# Main_Board_Smart_Door.net
KiCad netlist of a schematic drawn in EAGLE
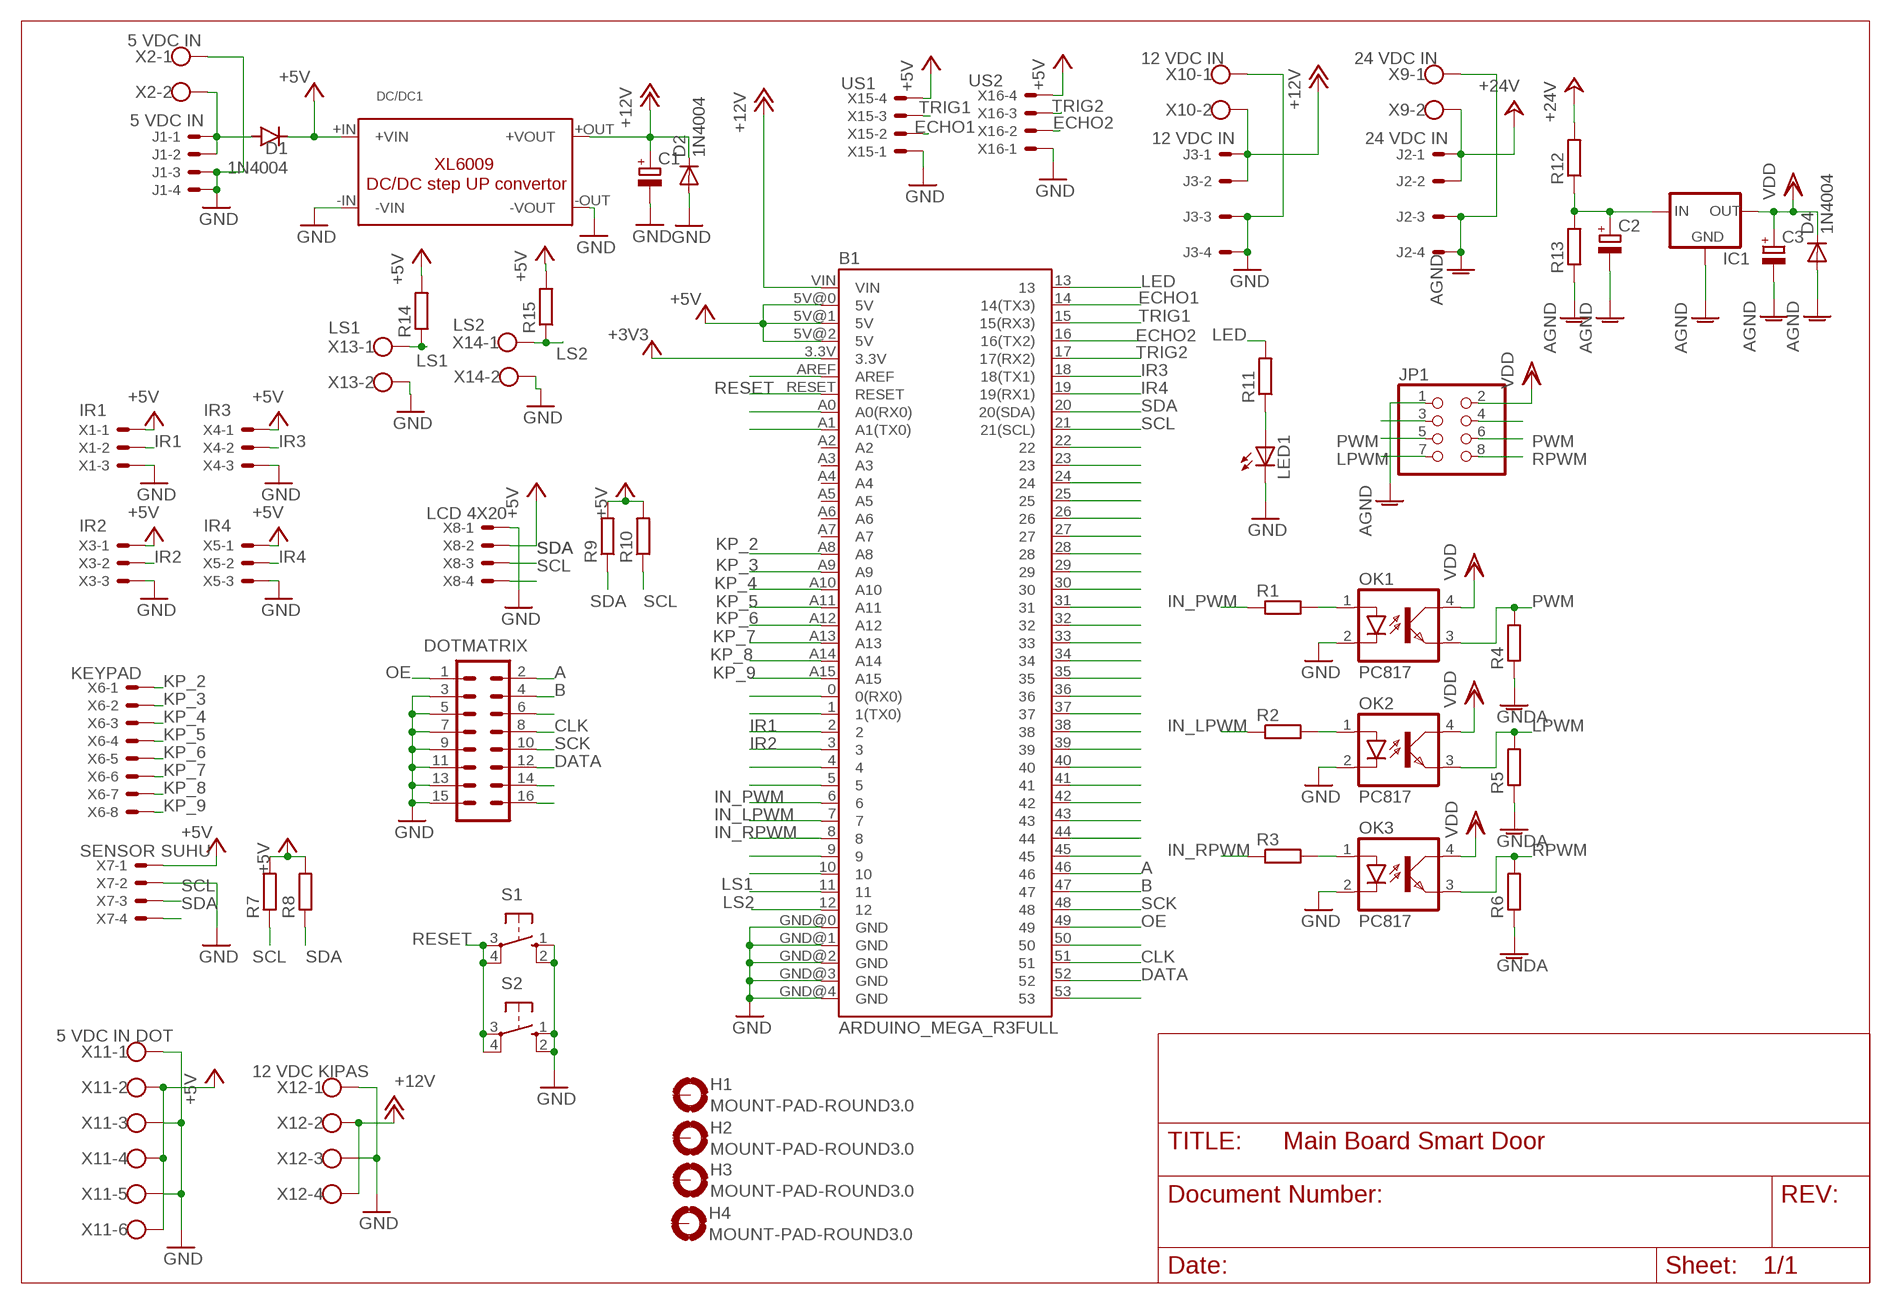
[diagram p0: schematic, sheet 1]

(export (version "E")
  (design (tool "Eeschema 10.0.6"))
  (components
    (comp (ref "B1")
      (value "ARDUINO_MEGA_R3FULL")
      (footprint "eagle-import:ARDUINO_MEGA")
      (libsource (lib "eagle-import") (part "ARDUINO_MEGA_R3FULL"))
    )
    (comp (ref "C1")
      (value "C-POL_RADIAL-25MM-DIA")
      (footprint "eagle-import:CAPPRD550W110D1250H2500B")
      (libsource (lib "eagle-import") (part "C-POLRADIAL-25MM-DIA_"))
    )
    (comp (ref "C2")
      (value "C-POL_RADIAL-25MM-DIA")
      (footprint "eagle-import:CAPPRD550W110D1250H2500B")
      (libsource (lib "eagle-import") (part "C-POLRADIAL-25MM-DIA_"))
    )
    (comp (ref "C3")
      (value "C-POL_RADIAL-25MM-DIA")
      (footprint "eagle-import:CAPPRD550W110D1250H2500B")
      (libsource (lib "eagle-import") (part "C-POLRADIAL-25MM-DIA_"))
    )
    (comp (ref "D1")
      (value "1N4004")
      (footprint "eagle-import:DO41-10")
      (libsource (lib "eagle-import") (part "diode_210_1N4004"))
    )
    (comp (ref "D2")
      (value "1N4004")
      (footprint "eagle-import:DO41-10")
      (libsource (lib "eagle-import") (part "1N4004"))
    )
    (comp (ref "D4")
      (value "1N4004")
      (footprint "eagle-import:DO41-10")
      (libsource (lib "eagle-import") (part "1N4004"))
    )
    (comp (ref "DC/DC1")
      (value "DC/DC-STEP-UP-XL6009")
      (footprint "eagle-import:DC_DC-STEP-UP-XL6009")
      (libsource (lib "eagle-import") (part "DC/DC-STEP-UP-XL6009"))
    )
    (comp (ref "DOTMATRIX")
      (value "ML16")
      (footprint "eagle-import:ML16")
      (libsource (lib "eagle-import") (part "ML16"))
    )
    (comp (ref "H1")
      (value "MOUNT-PAD-ROUND3.0")
      (footprint "eagle-import:3,0-PAD")
      (libsource (lib "eagle-import") (part "MOUNT-PAD-ROUND3.0"))
    )
    (comp (ref "H2")
      (value "MOUNT-PAD-ROUND3.0")
      (footprint "eagle-import:3,0-PAD")
      (libsource (lib "eagle-import") (part "MOUNT-PAD-ROUND3.0"))
    )
    (comp (ref "H3")
      (value "MOUNT-PAD-ROUND3.0")
      (footprint "eagle-import:3,0-PAD")
      (libsource (lib "eagle-import") (part "MOUNT-PAD-ROUND3.0"))
    )
    (comp (ref "H4")
      (value "MOUNT-PAD-ROUND3.0")
      (footprint "eagle-import:3,0-PAD")
      (libsource (lib "eagle-import") (part "MOUNT-PAD-ROUND3.0"))
    )
    (comp (ref "IC1")
      (value "78XXL")
      (footprint "eagle-import:78XXL")
      (libsource (lib "eagle-import") (part "78XXL"))
    )
    (comp (ref "J1")
      (value "5 VDC IN")
      (footprint "eagle-import:6410-04")
      (fields (field (name "MF") "MOLEX"))
      (libsource (lib "eagle-import") (part "22-?-0427-2041"))
    )
    (comp (ref "J2")
      (value "24 VDC IN")
      (footprint "eagle-import:6410-04")
      (fields (field (name "MF") "MOLEX"))
      (libsource (lib "eagle-import") (part "22-?-0427-2041"))
    )
    (comp (ref "J3")
      (value "12 VDC IN")
      (footprint "eagle-import:6410-04")
      (fields (field (name "MF") "MOLEX"))
      (libsource (lib "eagle-import") (part "22-?-0427-2041"))
    )
    (comp (ref "JP1")
      (value "PINHD-2X4")
      (footprint "eagle-import:2X04")
      (libsource (lib "eagle-import") (part "PINHD-2X4"))
    )
    (comp (ref "LED1")
      (value "LED5MM")
      (footprint "eagle-import:LED5MM")
      (libsource (lib "eagle-import") (part "LED5MM"))
    )
    (comp (ref "OK1")
      (value "PC817")
      (footprint "eagle-import:DIL04")
      (fields (field (name "MPN") "PC817X4J000F"))
      (libsource (lib "eagle-import") (part "PC817"))
    )
    (comp (ref "OK2")
      (value "PC817")
      (footprint "eagle-import:DIL04")
      (fields (field (name "MPN") "PC817X4J000F"))
      (libsource (lib "eagle-import") (part "PC817"))
    )
    (comp (ref "OK3")
      (value "PC817")
      (footprint "eagle-import:DIL04")
      (fields (field (name "MPN") "PC817X4J000F"))
      (libsource (lib "eagle-import") (part "PC817"))
    )
    (comp (ref "R1")
      (value "R-EU_0207/10")
      (footprint "eagle-import:0207_10")
      (libsource (lib "eagle-import") (part "R-EU_0207/10"))
    )
    (comp (ref "R2")
      (value "R-EU_0207/10")
      (footprint "eagle-import:0207_10")
      (libsource (lib "eagle-import") (part "R-EU_0207/10"))
    )
    (comp (ref "R3")
      (value "R-EU_0207/10")
      (footprint "eagle-import:0207_10")
      (libsource (lib "eagle-import") (part "R-EU_0207/10"))
    )
    (comp (ref "R4")
      (value "R-EU_0207/10")
      (footprint "eagle-import:0207_10")
      (libsource (lib "eagle-import") (part "R-EU_0207/10"))
    )
    (comp (ref "R5")
      (value "R-EU_0207/10")
      (footprint "eagle-import:0207_10")
      (libsource (lib "eagle-import") (part "R-EU_0207/10"))
    )
    (comp (ref "R6")
      (value "R-EU_0207/10")
      (footprint "eagle-import:0207_10")
      (libsource (lib "eagle-import") (part "R-EU_0207/10"))
    )
    (comp (ref "R7")
      (value "R-EU_0207/10")
      (footprint "eagle-import:0207_10")
      (libsource (lib "eagle-import") (part "R-EU_0207/10"))
    )
    (comp (ref "R8")
      (value "R-EU_0207/10")
      (footprint "eagle-import:0207_10")
      (libsource (lib "eagle-import") (part "R-EU_0207/10"))
    )
    (comp (ref "R9")
      (value "R-EU_0207/10")
      (footprint "eagle-import:0207_10")
      (libsource (lib "eagle-import") (part "R-EU_0207/10"))
    )
    (comp (ref "R10")
      (value "R-EU_0207/10")
      (footprint "eagle-import:0207_10")
      (libsource (lib "eagle-import") (part "R-EU_0207/10"))
    )
    (comp (ref "R11")
      (value "R-EU_0207/10")
      (footprint "eagle-import:0207_10")
      (libsource (lib "eagle-import") (part "R-EU_0207/10"))
    )
    (comp (ref "R12")
      (value "R-EU_0207/10")
      (footprint "eagle-import:0207_10")
      (libsource (lib "eagle-import") (part "R-EU_0207/10"))
    )
    (comp (ref "R13")
      (value "R-EU_0207/10")
      (footprint "eagle-import:0207_10")
      (libsource (lib "eagle-import") (part "R-EU_0207/10"))
    )
    (comp (ref "R14")
      (value "R-EU_0207/10")
      (footprint "eagle-import:0207_10")
      (libsource (lib "eagle-import") (part "R-EU_0207/10"))
    )
    (comp (ref "R15")
      (value "R-EU_0207/10")
      (footprint "eagle-import:0207_10")
      (libsource (lib "eagle-import") (part "R-EU_0207/10"))
    )
    (comp (ref "S1")
      (value "40-XX")
      (footprint "eagle-import:B3F-40XX")
      (fields (field (name "MF") "OMRON COMPONENTS USA") (field (name "MPN") "B3F-4000"))
      (libsource (lib "eagle-import") (part "40-XX"))
    )
    (comp (ref "S2")
      (value "10-XX")
      (footprint "eagle-import:B3F-10XX")
      (fields (field (name "MPN") "B3F-1000"))
      (libsource (lib "eagle-import") (part "10-XX"))
    )
    (comp (ref "X1")
      (value "IR1")
      (footprint "eagle-import:JST-XH-03-PACKAGE-LONG-PAD")
      (libsource (lib "eagle-import") (part "JST-XH-03-PIN-LONG-PAD"))
    )
    (comp (ref "X2")
      (value "5 VDC IN")
      (footprint "eagle-import:W237-102")
      (fields (field (name "MPN") "237-102"))
      (libsource (lib "eagle-import") (part "W237-102"))
    )
    (comp (ref "X3")
      (value "IR2")
      (footprint "eagle-import:JST-XH-03-PACKAGE-LONG-PAD")
      (libsource (lib "eagle-import") (part "JST-XH-03-PIN-LONG-PAD"))
    )
    (comp (ref "X4")
      (value "IR3")
      (footprint "eagle-import:JST-XH-03-PACKAGE-LONG-PAD")
      (libsource (lib "eagle-import") (part "JST-XH-03-PIN-LONG-PAD"))
    )
    (comp (ref "X5")
      (value "IR4")
      (footprint "eagle-import:JST-XH-03-PACKAGE-LONG-PAD")
      (libsource (lib "eagle-import") (part "JST-XH-03-PIN-LONG-PAD"))
    )
    (comp (ref "X6")
      (value "KEYPAD")
      (footprint "eagle-import:JST-XH-08-PACKAGE-LONG-PAD")
      (libsource (lib "eagle-import") (part "JST-XH-08-PIN-LONG-PAD"))
    )
    (comp (ref "X7")
      (value "SENSOR SUHU")
      (footprint "eagle-import:JST-XH-04-PACKAGE-LONG-PAD")
      (libsource (lib "eagle-import") (part "JST-XH-04-PIN-LONG-PAD"))
    )
    (comp (ref "X8")
      (value "LCD 4X20")
      (footprint "eagle-import:JST-XH-04-PACKAGE-LONG-PAD")
      (libsource (lib "eagle-import") (part "JST-XH-04-PIN-LONG-PAD"))
    )
    (comp (ref "X9")
      (value "24 VDC IN")
      (footprint "eagle-import:W237-102")
      (fields (field (name "MPN") "237-102"))
      (libsource (lib "eagle-import") (part "W237-102"))
    )
    (comp (ref "X10")
      (value "12 VDC IN")
      (footprint "eagle-import:W237-102")
      (fields (field (name "MPN") "237-102"))
      (libsource (lib "eagle-import") (part "W237-102"))
    )
    (comp (ref "X11")
      (value "5 VDC IN DOT")
      (footprint "eagle-import:W237-6")
      (libsource (lib "eagle-import") (part "W237-6"))
    )
    (comp (ref "X12")
      (value "12 VDC KIPAS")
      (footprint "eagle-import:W237-4")
      (libsource (lib "eagle-import") (part "W237-4"))
    )
    (comp (ref "X13")
      (value "LS1")
      (footprint "eagle-import:W237-102")
      (fields (field (name "MPN") "237-102"))
      (libsource (lib "eagle-import") (part "W237-102"))
    )
    (comp (ref "X14")
      (value "LS2")
      (footprint "eagle-import:W237-102")
      (fields (field (name "MPN") "237-102"))
      (libsource (lib "eagle-import") (part "W237-102"))
    )
    (comp (ref "X15")
      (value "US1")
      (footprint "eagle-import:JST-XH-04-PACKAGE-LONG-PAD")
      (libsource (lib "eagle-import") (part "JST-XH-04-PIN-LONG-PAD"))
    )
    (comp (ref "X16")
      (value "US2")
      (footprint "eagle-import:JST-XH-04-PACKAGE-LONG-PAD")
      (libsource (lib "eagle-import") (part "JST-XH-04-PIN-LONG-PAD"))
    )
  )
  (nets
    (net (code "1") (name "+3V3") (class "Default")
      (node (ref "B1") (pin "3.3V") (pinfunction "3.3V_3.3V") (pintype "bidirectional"))
    )
    (net (code "2") (name "+5V") (class "Default")
      (node (ref "B1") (pin "5V@0") (pinfunction "5V_5V@0") (pintype "bidirectional"))
      (node (ref "B1") (pin "5V@1") (pinfunction "5V_5V@1") (pintype "bidirectional"))
      (node (ref "B1") (pin "5V@2") (pinfunction "5V_5V@2") (pintype "bidirectional"))
      (node (ref "D1") (pin "C") (pinfunction "C_C") (pintype "passive"))
      (node (ref "DC/DC1") (pin "+IN") (pinfunction "+VIN_+IN") (pintype "bidirectional"))
      (node (ref "R10") (pin "2") (pinfunction "2_2") (pintype "passive"))
      (node (ref "R14") (pin "2") (pinfunction "2_2") (pintype "passive"))
      (node (ref "R15") (pin "2") (pinfunction "2_2") (pintype "passive"))
      (node (ref "R7") (pin "2") (pinfunction "2_2") (pintype "passive"))
      (node (ref "R8") (pin "2") (pinfunction "2_2") (pintype "passive"))
      (node (ref "R9") (pin "2") (pinfunction "2_2") (pintype "passive"))
      (node (ref "X1") (pin "1") (pinfunction "S_1") (pintype "passive"))
      (node (ref "X11") (pin "2") (pinfunction "KL_2") (pintype "passive"))
      (node (ref "X11") (pin "4") (pinfunction "KL_4") (pintype "passive"))
      (node (ref "X11") (pin "6") (pinfunction "KL_6") (pintype "passive"))
      (node (ref "X15") (pin "4") (pinfunction "S_4") (pintype "passive"))
      (node (ref "X16") (pin "4") (pinfunction "S_4") (pintype "passive"))
      (node (ref "X3") (pin "1") (pinfunction "S_1") (pintype "passive"))
      (node (ref "X4") (pin "1") (pinfunction "S_1") (pintype "passive"))
      (node (ref "X5") (pin "1") (pinfunction "S_1") (pintype "passive"))
      (node (ref "X7") (pin "1") (pinfunction "S_1") (pintype "passive"))
      (node (ref "X8") (pin "2") (pinfunction "S_2") (pintype "passive"))
    )
    (net (code "3") (name "+12V") (class "Default")
      (node (ref "B1") (pin "VIN") (pinfunction "VIN_VIN") (pintype "bidirectional"))
      (node (ref "C1") (pin "1") (pinfunction "+_1") (pintype "passive"))
      (node (ref "D2") (pin "C") (pinfunction "C_C") (pintype "passive"))
      (node (ref "DC/DC1") (pin "+OUT") (pinfunction "+VOUT_+OUT") (pintype "bidirectional"))
      (node (ref "J3") (pin "1") (pinfunction "S_1") (pintype "passive"))
      (node (ref "J3") (pin "2") (pinfunction "S_2") (pintype "passive"))
      (node (ref "X10") (pin "2") (pinfunction "KL_2") (pintype "passive"))
      (node (ref "X12") (pin "2") (pinfunction "KL_2") (pintype "passive"))
      (node (ref "X12") (pin "4") (pinfunction "KL_4") (pintype "passive"))
    )
    (net (code "4") (name "+24V") (class "Default")
      (node (ref "J2") (pin "1") (pinfunction "S_1") (pintype "passive"))
      (node (ref "J2") (pin "2") (pinfunction "S_2") (pintype "passive"))
      (node (ref "R12") (pin "2") (pinfunction "2_2") (pintype "passive"))
      (node (ref "X9") (pin "2") (pinfunction "KL_2") (pintype "passive"))
    )
    (net (code "5") (name "/A") (class "Default")
      (node (ref "B1") (pin "46") (pinfunction "46_46") (pintype "bidirectional"))
      (node (ref "DOTMATRIX") (pin "2") (pinfunction "2_2") (pintype "passive"))
    )
    (net (code "6") (name "/B") (class "Default")
      (node (ref "B1") (pin "47") (pinfunction "47_47") (pintype "bidirectional"))
      (node (ref "DOTMATRIX") (pin "4") (pinfunction "4_4") (pintype "passive"))
    )
    (net (code "7") (name "/CLK") (class "Default")
      (node (ref "B1") (pin "51") (pinfunction "51_51") (pintype "bidirectional"))
      (node (ref "DOTMATRIX") (pin "8") (pinfunction "8_8") (pintype "passive"))
    )
    (net (code "8") (name "/DATA") (class "Default")
      (node (ref "B1") (pin "52") (pinfunction "52_52") (pintype "bidirectional"))
      (node (ref "DOTMATRIX") (pin "12") (pinfunction "12_12") (pintype "passive"))
    )
    (net (code "9") (name "/ECHO1") (class "Default")
      (node (ref "B1") (pin "14") (pinfunction "14(TX3)_14") (pintype "bidirectional"))
      (node (ref "X15") (pin "2") (pinfunction "S_2") (pintype "passive"))
    )
    (net (code "10") (name "/ECHO2") (class "Default")
      (node (ref "B1") (pin "16") (pinfunction "16(TX2)_16") (pintype "bidirectional"))
      (node (ref "X16") (pin "2") (pinfunction "S_2") (pintype "passive"))
    )
    (net (code "11") (name "/IN_LPWM") (class "Default")
      (node (ref "B1") (pin "7") (pinfunction "7_7") (pintype "bidirectional"))
      (node (ref "R2") (pin "1") (pinfunction "1_1") (pintype "passive"))
    )
    (net (code "12") (name "/IN_PWM") (class "Default")
      (node (ref "B1") (pin "6") (pinfunction "6_6") (pintype "bidirectional"))
      (node (ref "R1") (pin "1") (pinfunction "1_1") (pintype "passive"))
    )
    (net (code "13") (name "/IN_RPWM") (class "Default")
      (node (ref "B1") (pin "8") (pinfunction "8_8") (pintype "bidirectional"))
      (node (ref "R3") (pin "1") (pinfunction "1_1") (pintype "passive"))
    )
    (net (code "14") (name "/IR1") (class "Default")
      (node (ref "B1") (pin "2") (pinfunction "2_2") (pintype "bidirectional"))
      (node (ref "X1") (pin "2") (pinfunction "S_2") (pintype "passive"))
    )
    (net (code "15") (name "/IR2") (class "Default")
      (node (ref "B1") (pin "3") (pinfunction "3_3") (pintype "bidirectional"))
      (node (ref "X3") (pin "2") (pinfunction "S_2") (pintype "passive"))
    )
    (net (code "16") (name "/IR3") (class "Default")
      (node (ref "B1") (pin "18") (pinfunction "18(TX1)_18") (pintype "bidirectional"))
      (node (ref "X4") (pin "2") (pinfunction "S_2") (pintype "passive"))
    )
    (net (code "17") (name "/IR4") (class "Default")
      (node (ref "B1") (pin "19") (pinfunction "19(RX1)_19") (pintype "bidirectional"))
      (node (ref "X5") (pin "2") (pinfunction "S_2") (pintype "passive"))
    )
    (net (code "18") (name "/KP_2") (class "Default")
      (node (ref "B1") (pin "A8") (pinfunction "A8_A8") (pintype "bidirectional"))
      (node (ref "X6") (pin "1") (pinfunction "S_1") (pintype "passive"))
    )
    (net (code "19") (name "/KP_3") (class "Default")
      (node (ref "B1") (pin "A9") (pinfunction "A9_A9") (pintype "bidirectional"))
      (node (ref "X6") (pin "2") (pinfunction "S_2") (pintype "passive"))
    )
    (net (code "20") (name "/KP_4") (class "Default")
      (node (ref "B1") (pin "A10") (pinfunction "A10_A10") (pintype "bidirectional"))
      (node (ref "X6") (pin "3") (pinfunction "S_3") (pintype "passive"))
    )
    (net (code "21") (name "/KP_5") (class "Default")
      (node (ref "B1") (pin "A11") (pinfunction "A11_A11") (pintype "bidirectional"))
      (node (ref "X6") (pin "4") (pinfunction "S_4") (pintype "passive"))
    )
    (net (code "22") (name "/KP_6") (class "Default")
      (node (ref "B1") (pin "A12") (pinfunction "A12_A12") (pintype "bidirectional"))
      (node (ref "X6") (pin "5") (pinfunction "S_5") (pintype "passive"))
    )
    (net (code "23") (name "/KP_7") (class "Default")
      (node (ref "B1") (pin "A13") (pinfunction "A13_A13") (pintype "bidirectional"))
      (node (ref "X6") (pin "6") (pinfunction "S_6") (pintype "passive"))
    )
    (net (code "24") (name "/KP_8") (class "Default")
      (node (ref "B1") (pin "A14") (pinfunction "A14_A14") (pintype "bidirectional"))
      (node (ref "X6") (pin "7") (pinfunction "S_7") (pintype "passive"))
    )
    (net (code "25") (name "/KP_9") (class "Default")
      (node (ref "B1") (pin "A15") (pinfunction "A15_A15") (pintype "bidirectional"))
      (node (ref "X6") (pin "8") (pinfunction "S_8") (pintype "passive"))
    )
    (net (code "26") (name "/LED") (class "Default")
      (node (ref "B1") (pin "13") (pinfunction "13_13") (pintype "bidirectional"))
      (node (ref "R11") (pin "2") (pinfunction "2_2") (pintype "passive"))
    )
    (net (code "27") (name "/LPWM") (class "Default")
      (node (ref "JP1") (pin "7") (pinfunction "7_7") (pintype "passive"))
      (node (ref "OK2") (pin "3") (pinfunction "EMIT_3") (pintype "passive"))
      (node (ref "R5") (pin "2") (pinfunction "2_2") (pintype "passive"))
    )
    (net (code "28") (name "/LS1") (class "Default")
      (node (ref "B1") (pin "11") (pinfunction "11_11") (pintype "bidirectional"))
      (node (ref "R14") (pin "1") (pinfunction "1_1") (pintype "passive"))
      (node (ref "X13") (pin "1") (pinfunction "KL_1") (pintype "passive"))
    )
    (net (code "29") (name "/LS2") (class "Default")
      (node (ref "B1") (pin "12") (pinfunction "12_12") (pintype "bidirectional"))
      (node (ref "R15") (pin "1") (pinfunction "1_1") (pintype "passive"))
      (node (ref "X14") (pin "1") (pinfunction "KL_1") (pintype "passive"))
    )
    (net (code "30") (name "/OE") (class "Default")
      (node (ref "B1") (pin "49") (pinfunction "49_49") (pintype "bidirectional"))
      (node (ref "DOTMATRIX") (pin "1") (pinfunction "1_1") (pintype "passive"))
    )
    (net (code "31") (name "/PWM") (class "Default")
      (node (ref "JP1") (pin "5") (pinfunction "5_5") (pintype "passive"))
      (node (ref "JP1") (pin "6") (pinfunction "6_6") (pintype "passive"))
      (node (ref "OK1") (pin "3") (pinfunction "EMIT_3") (pintype "passive"))
      (node (ref "R4") (pin "2") (pinfunction "2_2") (pintype "passive"))
    )
    (net (code "32") (name "/RESET") (class "Default")
      (node (ref "B1") (pin "RESET") (pinfunction "RESET_RESET") (pintype "bidirectional"))
      (node (ref "S1") (pin "3") (pinfunction "P_3") (pintype "passive"))
      (node (ref "S1") (pin "4") (pinfunction "P1_4") (pintype "passive"))
      (node (ref "S2") (pin "3") (pinfunction "P_3") (pintype "passive"))
      (node (ref "S2") (pin "4") (pinfunction "P1_4") (pintype "passive"))
    )
    (net (code "33") (name "/RPWM") (class "Default")
      (node (ref "JP1") (pin "8") (pinfunction "8_8") (pintype "passive"))
      (node (ref "OK3") (pin "3") (pinfunction "EMIT_3") (pintype "passive"))
      (node (ref "R6") (pin "2") (pinfunction "2_2") (pintype "passive"))
    )
    (net (code "34") (name "/SCK") (class "Default")
      (node (ref "B1") (pin "48") (pinfunction "48_48") (pintype "bidirectional"))
      (node (ref "DOTMATRIX") (pin "10") (pinfunction "10_10") (pintype "passive"))
    )
    (net (code "35") (name "/SCL") (class "Default")
      (node (ref "B1") (pin "21") (pinfunction "21(SCL)_21") (pintype "bidirectional"))
      (node (ref "R10") (pin "1") (pinfunction "1_1") (pintype "passive"))
      (node (ref "R7") (pin "1") (pinfunction "1_1") (pintype "passive"))
      (node (ref "X7") (pin "3") (pinfunction "S_3") (pintype "passive"))
      (node (ref "X8") (pin "4") (pinfunction "S_4") (pintype "passive"))
    )
    (net (code "36") (name "/SDA") (class "Default")
      (node (ref "B1") (pin "20") (pinfunction "20(SDA)_20") (pintype "bidirectional"))
      (node (ref "R8") (pin "1") (pinfunction "1_1") (pintype "passive"))
      (node (ref "R9") (pin "1") (pinfunction "1_1") (pintype "passive"))
      (node (ref "X7") (pin "4") (pinfunction "S_4") (pintype "passive"))
      (node (ref "X8") (pin "3") (pinfunction "S_3") (pintype "passive"))
    )
    (net (code "37") (name "/TRIG1") (class "Default")
      (node (ref "B1") (pin "15") (pinfunction "15(RX3)_15") (pintype "bidirectional"))
      (node (ref "X15") (pin "3") (pinfunction "S_3") (pintype "passive"))
    )
    (net (code "38") (name "/TRIG2") (class "Default")
      (node (ref "B1") (pin "17") (pinfunction "17(RX2)_17") (pintype "bidirectional"))
      (node (ref "X16") (pin "3") (pinfunction "S_3") (pintype "passive"))
    )
    (net (code "39") (name "AGND") (class "Default")
      (node (ref "C2") (pin "2") (pinfunction "-_2") (pintype "passive"))
      (node (ref "C3") (pin "2") (pinfunction "-_2") (pintype "passive"))
      (node (ref "D4") (pin "A") (pinfunction "A_A") (pintype "passive"))
      (node (ref "IC1") (pin "GND") (pinfunction "GND_GND") (pintype "input"))
      (node (ref "J2") (pin "3") (pinfunction "S_3") (pintype "passive"))
      (node (ref "J2") (pin "4") (pinfunction "S_4") (pintype "passive"))
      (node (ref "JP1") (pin "1") (pinfunction "1_1") (pintype "passive"))
      (node (ref "R13") (pin "1") (pinfunction "1_1") (pintype "passive"))
      (node (ref "X9") (pin "1") (pinfunction "KL_1") (pintype "passive"))
    )
    (net (code "40") (name "GND") (class "Default")
      (node (ref "B1") (pin "GND@0") (pinfunction "GND_GND@0") (pintype "bidirectional"))
      (node (ref "B1") (pin "GND@1") (pinfunction "GND_GND@1") (pintype "bidirectional"))
      (node (ref "B1") (pin "GND@2") (pinfunction "GND_GND@2") (pintype "bidirectional"))
      (node (ref "B1") (pin "GND@3") (pinfunction "GND_GND@3") (pintype "bidirectional"))
      (node (ref "B1") (pin "GND@4") (pinfunction "GND_GND@4") (pintype "bidirectional"))
      (node (ref "C1") (pin "2") (pinfunction "-_2") (pintype "passive"))
      (node (ref "D2") (pin "A") (pinfunction "A_A") (pintype "passive"))
      (node (ref "DC/DC1") (pin "-IN") (pinfunction "-VIN_-IN") (pintype "bidirectional"))
      (node (ref "DC/DC1") (pin "-OUT") (pinfunction "-VOUT_-OUT") (pintype "bidirectional"))
      (node (ref "DOTMATRIX") (pin "11") (pinfunction "11_11") (pintype "passive"))
      (node (ref "DOTMATRIX") (pin "13") (pinfunction "13_13") (pintype "passive"))
      (node (ref "DOTMATRIX") (pin "15") (pinfunction "15_15") (pintype "passive"))
      (node (ref "DOTMATRIX") (pin "3") (pinfunction "3_3") (pintype "passive"))
      (node (ref "DOTMATRIX") (pin "5") (pinfunction "5_5") (pintype "passive"))
      (node (ref "DOTMATRIX") (pin "7") (pinfunction "7_7") (pintype "passive"))
      (node (ref "DOTMATRIX") (pin "9") (pinfunction "9_9") (pintype "passive"))
      (node (ref "J1") (pin "3") (pinfunction "S_3") (pintype "passive"))
      (node (ref "J1") (pin "4") (pinfunction "S_4") (pintype "passive"))
      (node (ref "J3") (pin "3") (pinfunction "S_3") (pintype "passive"))
      (node (ref "J3") (pin "4") (pinfunction "S_4") (pintype "passive"))
      (node (ref "LED1") (pin "K") (pinfunction "C_K") (pintype "passive"))
      (node (ref "OK1") (pin "2") (pinfunction "C_2") (pintype "passive"))
      (node (ref "OK2") (pin "2") (pinfunction "C_2") (pintype "passive"))
      (node (ref "OK3") (pin "2") (pinfunction "C_2") (pintype "passive"))
      (node (ref "S1") (pin "1") (pinfunction "S_1") (pintype "passive"))
      (node (ref "S1") (pin "2") (pinfunction "S1_2") (pintype "passive"))
      (node (ref "S2") (pin "1") (pinfunction "S_1") (pintype "passive"))
      (node (ref "S2") (pin "2") (pinfunction "S1_2") (pintype "passive"))
      (node (ref "X1") (pin "3") (pinfunction "S_3") (pintype "passive"))
      (node (ref "X10") (pin "1") (pinfunction "KL_1") (pintype "passive"))
      (node (ref "X11") (pin "1") (pinfunction "KL_1") (pintype "passive"))
      (node (ref "X11") (pin "3") (pinfunction "KL_3") (pintype "passive"))
      (node (ref "X11") (pin "5") (pinfunction "KL_5") (pintype "passive"))
      (node (ref "X12") (pin "1") (pinfunction "KL_1") (pintype "passive"))
      (node (ref "X12") (pin "3") (pinfunction "KL_3") (pintype "passive"))
      (node (ref "X13") (pin "2") (pinfunction "KL_2") (pintype "passive"))
      (node (ref "X14") (pin "2") (pinfunction "KL_2") (pintype "passive"))
      (node (ref "X15") (pin "1") (pinfunction "S_1") (pintype "passive"))
      (node (ref "X16") (pin "1") (pinfunction "S_1") (pintype "passive"))
      (node (ref "X2") (pin "1") (pinfunction "KL_1") (pintype "passive"))
      (node (ref "X3") (pin "3") (pinfunction "S_3") (pintype "passive"))
      (node (ref "X4") (pin "3") (pinfunction "S_3") (pintype "passive"))
      (node (ref "X5") (pin "3") (pinfunction "S_3") (pintype "passive"))
      (node (ref "X7") (pin "2") (pinfunction "S_2") (pintype "passive"))
      (node (ref "X8") (pin "1") (pinfunction "S_1") (pintype "passive"))
    )
    (net (code "41") (name "GNDA") (class "Default")
      (node (ref "R4") (pin "1") (pinfunction "1_1") (pintype "passive"))
      (node (ref "R5") (pin "1") (pinfunction "1_1") (pintype "passive"))
      (node (ref "R6") (pin "1") (pinfunction "1_1") (pintype "passive"))
    )
    (net (code "42") (name "Net-(C2-+)") (class "Default")
      (node (ref "C2") (pin "1") (pinfunction "+_1") (pintype "passive"))
      (node (ref "IC1") (pin "IN") (pinfunction "IN_IN") (pintype "input"))
      (node (ref "R12") (pin "1") (pinfunction "1_1") (pintype "passive"))
      (node (ref "R13") (pin "2") (pinfunction "2_2") (pintype "passive"))
    )
    (net (code "43") (name "Net-(J1A-S)") (class "Default")
      (node (ref "D1") (pin "A") (pinfunction "A_A") (pintype "passive"))
      (node (ref "J1") (pin "1") (pinfunction "S_1") (pintype "passive"))
      (node (ref "J1") (pin "2") (pinfunction "S_2") (pintype "passive"))
      (node (ref "X2") (pin "2") (pinfunction "KL_2") (pintype "passive"))
    )
    (net (code "44") (name "Net-(LED1-PadA)") (class "Default")
      (node (ref "LED1") (pin "A") (pinfunction "A_A") (pintype "passive"))
      (node (ref "R11") (pin "1") (pinfunction "1_1") (pintype "passive"))
    )
    (net (code "45") (name "Net-(OK1-A)") (class "Default")
      (node (ref "OK1") (pin "1") (pinfunction "A_1") (pintype "passive"))
      (node (ref "R1") (pin "2") (pinfunction "2_2") (pintype "passive"))
    )
    (net (code "46") (name "Net-(OK2-A)") (class "Default")
      (node (ref "OK2") (pin "1") (pinfunction "A_1") (pintype "passive"))
      (node (ref "R2") (pin "2") (pinfunction "2_2") (pintype "passive"))
    )
    (net (code "47") (name "Net-(OK3-A)") (class "Default")
      (node (ref "OK3") (pin "1") (pinfunction "A_1") (pintype "passive"))
      (node (ref "R3") (pin "2") (pinfunction "2_2") (pintype "passive"))
    )
    (net (code "48") (name "VDD") (class "Default")
      (node (ref "C3") (pin "1") (pinfunction "+_1") (pintype "passive"))
      (node (ref "D4") (pin "C") (pinfunction "C_C") (pintype "passive"))
      (node (ref "IC1") (pin "OUT") (pinfunction "OUT_OUT") (pintype "passive"))
      (node (ref "JP1") (pin "2") (pinfunction "2_2") (pintype "passive"))
      (node (ref "OK1") (pin "4") (pinfunction "COL_4") (pintype "passive"))
      (node (ref "OK2") (pin "4") (pinfunction "COL_4") (pintype "passive"))
      (node (ref "OK3") (pin "4") (pinfunction "COL_4") (pintype "passive"))
    )
    (net (code "49") (name "unconnected-(B1-0(RX0)-Pad0)") (class "Default")
      (node (ref "B1") (pin "0") (pinfunction "0(RX0)_0") (pintype "bidirectional"))
    )
    (net (code "50") (name "unconnected-(B1-1(TX0)-Pad1)") (class "Default")
      (node (ref "B1") (pin "1") (pinfunction "1(TX0)_1") (pintype "bidirectional"))
    )
    (net (code "51") (name "unconnected-(B1-A0(RX0)-PadA0)") (class "Default")
      (node (ref "B1") (pin "A0") (pinfunction "A0(RX0)_A0") (pintype "bidirectional"))
    )
    (net (code "52") (name "unconnected-(B1-A1(TX0)-PadA1)") (class "Default")
      (node (ref "B1") (pin "A1") (pinfunction "A1(TX0)_A1") (pintype "bidirectional"))
    )
    (net (code "53") (name "unconnected-(B1-Pad4)") (class "Default")
      (node (ref "B1") (pin "4") (pinfunction "4_4") (pintype "bidirectional"))
    )
    (net (code "54") (name "unconnected-(B1-Pad5)") (class "Default")
      (node (ref "B1") (pin "5") (pinfunction "5_5") (pintype "bidirectional"))
    )
    (net (code "55") (name "unconnected-(B1-Pad9)") (class "Default")
      (node (ref "B1") (pin "9") (pinfunction "9_9") (pintype "bidirectional"))
    )
    (net (code "56") (name "unconnected-(B1-Pad10)") (class "Default")
      (node (ref "B1") (pin "10") (pinfunction "10_10") (pintype "bidirectional"))
    )
    (net (code "57") (name "unconnected-(B1-Pad22)") (class "Default")
      (node (ref "B1") (pin "22") (pinfunction "22_22") (pintype "bidirectional"))
    )
    (net (code "58") (name "unconnected-(B1-Pad23)") (class "Default")
      (node (ref "B1") (pin "23") (pinfunction "23_23") (pintype "bidirectional"))
    )
    (net (code "59") (name "unconnected-(B1-Pad24)") (class "Default")
      (node (ref "B1") (pin "24") (pinfunction "24_24") (pintype "bidirectional"))
    )
    (net (code "60") (name "unconnected-(B1-Pad25)") (class "Default")
      (node (ref "B1") (pin "25") (pinfunction "25_25") (pintype "bidirectional"))
    )
    (net (code "61") (name "unconnected-(B1-Pad26)") (class "Default")
      (node (ref "B1") (pin "26") (pinfunction "26_26") (pintype "bidirectional"))
    )
    (net (code "62") (name "unconnected-(B1-Pad27)") (class "Default")
      (node (ref "B1") (pin "27") (pinfunction "27_27") (pintype "bidirectional"))
    )
    (net (code "63") (name "unconnected-(B1-Pad28)") (class "Default")
      (node (ref "B1") (pin "28") (pinfunction "28_28") (pintype "bidirectional"))
    )
    (net (code "64") (name "unconnected-(B1-Pad29)") (class "Default")
      (node (ref "B1") (pin "29") (pinfunction "29_29") (pintype "bidirectional"))
    )
    (net (code "65") (name "unconnected-(B1-Pad30)") (class "Default")
      (node (ref "B1") (pin "30") (pinfunction "30_30") (pintype "bidirectional"))
    )
    (net (code "66") (name "unconnected-(B1-Pad31)") (class "Default")
      (node (ref "B1") (pin "31") (pinfunction "31_31") (pintype "bidirectional"))
    )
    (net (code "67") (name "unconnected-(B1-Pad32)") (class "Default")
      (node (ref "B1") (pin "32") (pinfunction "32_32") (pintype "bidirectional"))
    )
    (net (code "68") (name "unconnected-(B1-Pad33)") (class "Default")
      (node (ref "B1") (pin "33") (pinfunction "33_33") (pintype "bidirectional"))
    )
    (net (code "69") (name "unconnected-(B1-Pad34)") (class "Default")
      (node (ref "B1") (pin "34") (pinfunction "34_34") (pintype "bidirectional"))
    )
    (net (code "70") (name "unconnected-(B1-Pad35)") (class "Default")
      (node (ref "B1") (pin "35") (pinfunction "35_35") (pintype "bidirectional"))
    )
    (net (code "71") (name "unconnected-(B1-Pad36)") (class "Default")
      (node (ref "B1") (pin "36") (pinfunction "36_36") (pintype "bidirectional"))
    )
    (net (code "72") (name "unconnected-(B1-Pad37)") (class "Default")
      (node (ref "B1") (pin "37") (pinfunction "37_37") (pintype "bidirectional"))
    )
    (net (code "73") (name "unconnected-(B1-Pad38)") (class "Default")
      (node (ref "B1") (pin "38") (pinfunction "38_38") (pintype "bidirectional"))
    )
    (net (code "74") (name "unconnected-(B1-Pad39)") (class "Default")
      (node (ref "B1") (pin "39") (pinfunction "39_39") (pintype "bidirectional"))
    )
    (net (code "75") (name "unconnected-(B1-Pad40)") (class "Default")
      (node (ref "B1") (pin "40") (pinfunction "40_40") (pintype "bidirectional"))
    )
    (net (code "76") (name "unconnected-(B1-Pad41)") (class "Default")
      (node (ref "B1") (pin "41") (pinfunction "41_41") (pintype "bidirectional"))
    )
    (net (code "77") (name "unconnected-(B1-Pad42)") (class "Default")
      (node (ref "B1") (pin "42") (pinfunction "42_42") (pintype "bidirectional"))
    )
    (net (code "78") (name "unconnected-(B1-Pad43)") (class "Default")
      (node (ref "B1") (pin "43") (pinfunction "43_43") (pintype "bidirectional"))
    )
    (net (code "79") (name "unconnected-(B1-Pad44)") (class "Default")
      (node (ref "B1") (pin "44") (pinfunction "44_44") (pintype "bidirectional"))
    )
    (net (code "80") (name "unconnected-(B1-Pad45)") (class "Default")
      (node (ref "B1") (pin "45") (pinfunction "45_45") (pintype "bidirectional"))
    )
    (net (code "81") (name "unconnected-(B1-Pad50)") (class "Default")
      (node (ref "B1") (pin "50") (pinfunction "50_50") (pintype "bidirectional"))
    )
    (net (code "82") (name "unconnected-(B1-Pad53)") (class "Default")
      (node (ref "B1") (pin "53") (pinfunction "53_53") (pintype "bidirectional"))
    )
    (net (code "83") (name "unconnected-(B1-PadA2)") (class "Default")
      (node (ref "B1") (pin "A2") (pinfunction "A2_A2") (pintype "bidirectional"))
    )
    (net (code "84") (name "unconnected-(B1-PadA3)") (class "Default")
      (node (ref "B1") (pin "A3") (pinfunction "A3_A3") (pintype "bidirectional"))
    )
    (net (code "85") (name "unconnected-(B1-PadA4)") (class "Default")
      (node (ref "B1") (pin "A4") (pinfunction "A4_A4") (pintype "bidirectional"))
    )
    (net (code "86") (name "unconnected-(B1-PadA5)") (class "Default")
      (node (ref "B1") (pin "A5") (pinfunction "A5_A5") (pintype "bidirectional"))
    )
    (net (code "87") (name "unconnected-(B1-PadA6)") (class "Default")
      (node (ref "B1") (pin "A6") (pinfunction "A6_A6") (pintype "bidirectional"))
    )
    (net (code "88") (name "unconnected-(B1-PadA7)") (class "Default")
      (node (ref "B1") (pin "A7") (pinfunction "A7_A7") (pintype "bidirectional"))
    )
    (net (code "89") (name "unconnected-(B1-PadAREF)") (class "Default")
      (node (ref "B1") (pin "AREF") (pinfunction "AREF_AREF") (pintype "bidirectional"))
    )
    (net (code "90") (name "unconnected-(DOTMATRIX-Pad6)") (class "Default")
      (node (ref "DOTMATRIX") (pin "6") (pinfunction "6_6") (pintype "passive"))
    )
    (net (code "91") (name "unconnected-(DOTMATRIX-Pad14)") (class "Default")
      (node (ref "DOTMATRIX") (pin "14") (pinfunction "14_14") (pintype "passive"))
    )
    (net (code "92") (name "unconnected-(DOTMATRIX-Pad16)") (class "Default")
      (node (ref "DOTMATRIX") (pin "16") (pinfunction "16_16") (pintype "passive"))
    )
    (net (code "93") (name "unconnected-(H1-MOUNT-PadB3,0)") (class "Default")
      (node (ref "H1") (pin "B3,0") (pinfunction "MOUNT_B3,0") (pintype "passive"))
    )
    (net (code "94") (name "unconnected-(H2-MOUNT-PadB3,0)") (class "Default")
      (node (ref "H2") (pin "B3,0") (pinfunction "MOUNT_B3,0") (pintype "passive"))
    )
    (net (code "95") (name "unconnected-(H3-MOUNT-PadB3,0)") (class "Default")
      (node (ref "H3") (pin "B3,0") (pinfunction "MOUNT_B3,0") (pintype "passive"))
    )
    (net (code "96") (name "unconnected-(H4-MOUNT-PadB3,0)") (class "Default")
      (node (ref "H4") (pin "B3,0") (pinfunction "MOUNT_B3,0") (pintype "passive"))
    )
    (net (code "97") (name "unconnected-(JP1-Pad3)") (class "Default")
      (node (ref "JP1") (pin "3") (pinfunction "3_3") (pintype "passive"))
    )
    (net (code "98") (name "unconnected-(JP1-Pad4)") (class "Default")
      (node (ref "JP1") (pin "4") (pinfunction "4_4") (pintype "passive"))
    )
  )
)
